# Port.net
KiCad netlist of a schematic drawn in Altium Designer
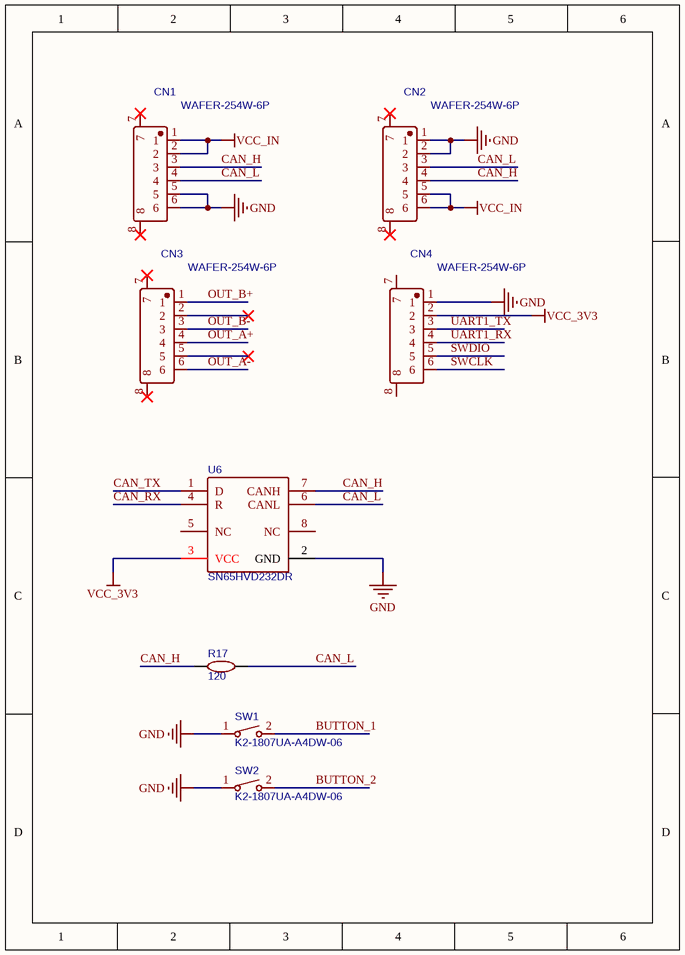
[diagram p0: Port.SchDoc]

(export (version "E")
  (design (tool "Eeschema 10.0.6"))
  (components
    (comp (ref "CN1")
      (value "WAFER-254W-6P")
      (footprint "CONN-SMD_WAFER-254W-6P")
      (fields (field (name "BOM_SUPPLIER PART") "C2856747") (field (name "CONTRIBUTOR") "LCSC"))
      (libsource (lib "6P 2.54mm") (part "WAFER-254W-6P"))
    )
    (comp (ref "CN2")
      (value "WAFER-254W-6P")
      (footprint "CONN-SMD_WAFER-254W-6P")
      (fields (field (name "BOM_SUPPLIER PART") "C2856747") (field (name "CONTRIBUTOR") "LCSC"))
      (libsource (lib "6P 2.54mm") (part "WAFER-254W-6P"))
    )
    (comp (ref "CN3")
      (value "WAFER-254W-6P")
      (footprint "CONN-SMD_WAFER-254W-6P")
      (fields (field (name "BOM_SUPPLIER PART") "C2856747") (field (name "CONTRIBUTOR") "LCSC"))
      (libsource (lib "6P 2.54mm") (part "WAFER-254W-6P"))
    )
    (comp (ref "CN4")
      (value "WAFER-254W-6P")
      (footprint "CONN-SMD_WAFER-254W-6P")
      (fields (field (name "BOM_SUPPLIER PART") "C2856747") (field (name "CONTRIBUTOR") "LCSC"))
      (libsource (lib "6P 2.54mm") (part "WAFER-254W-6P"))
    )
    (comp (ref "R17")
      (value "120")
      (footprint "R0603")
      (fields
        (field (name "BOM_MANUFACTURER PART") "0603WAF1200T5E")
        (field (name "BOM_SUPPLIER PART") "C22787")
      )
      (libsource (lib "120R") (part "120"))
    )
    (comp (ref "SW1")
      (value "K2-1807UA-A4DW-06")
      (footprint "KEY-SMD_L4.0-W2.9-L")
      (fields (field (name "BOM_SUPPLIER PART") "C502307") (field (name "CONTRIBUTOR") "LCSC"))
      (libsource (lib "BUTTON") (part "K2-1807UA-A4DW-06"))
    )
    (comp (ref "SW2")
      (value "K2-1807UA-A4DW-06")
      (footprint "KEY-SMD_L4.0-W2.9-L")
      (fields (field (name "BOM_SUPPLIER PART") "C502307") (field (name "CONTRIBUTOR") "LCSC"))
      (libsource (lib "BUTTON") (part "K2-1807UA-A4DW-06"))
    )
    (comp (ref "U6")
      (value "SN65HVD232DR")
      (footprint "SOIC-8_L5.0-W4.0-P1.27-LS6.0-BL")
      (fields (field (name "BOM_SUPPLIER PART") "C30530"))
      (libsource (lib "SN65HVD232DR") (part "SN65HVD232DR"))
    )
  )
  (nets
    (net (code "1") (name "/BUTTON_1") (class "Default")
      (node (ref "SW1") (pin "2") (pinfunction "2_2") (pintype "passive"))
    )
    (net (code "2") (name "/BUTTON_2") (class "Default")
      (node (ref "SW2") (pin "2") (pinfunction "2_2") (pintype "passive"))
    )
    (net (code "3") (name "/CAN_H") (class "Default")
      (node (ref "CN1") (pin "3") (pinfunction "3_3") (pintype "passive"))
      (node (ref "CN2") (pin "4") (pinfunction "4_4") (pintype "passive"))
      (node (ref "R17") (pin "1") (pinfunction "1_1") (pintype "passive"))
      (node (ref "U6") (pin "7") (pinfunction "CANH_7") (pintype "passive"))
    )
    (net (code "4") (name "/CAN_L") (class "Default")
      (node (ref "CN1") (pin "4") (pinfunction "4_4") (pintype "passive"))
      (node (ref "CN2") (pin "3") (pinfunction "3_3") (pintype "passive"))
      (node (ref "R17") (pin "2") (pinfunction "2_2") (pintype "passive"))
      (node (ref "U6") (pin "6") (pinfunction "CANL_6") (pintype "passive"))
    )
    (net (code "5") (name "/CAN_RX") (class "Default")
      (node (ref "U6") (pin "4") (pinfunction "R_4") (pintype "passive"))
    )
    (net (code "6") (name "/CAN_TX") (class "Default")
      (node (ref "U6") (pin "1") (pinfunction "D_1") (pintype "passive"))
    )
    (net (code "7") (name "/OUT_A+") (class "Default")
      (node (ref "CN3") (pin "4") (pinfunction "4_4") (pintype "passive"))
    )
    (net (code "8") (name "/OUT_A-") (class "Default")
      (node (ref "CN3") (pin "6") (pinfunction "6_6") (pintype "passive"))
    )
    (net (code "9") (name "/OUT_B+") (class "Default")
      (node (ref "CN3") (pin "1") (pinfunction "1_1") (pintype "passive"))
    )
    (net (code "10") (name "/OUT_B-") (class "Default")
      (node (ref "CN3") (pin "3") (pinfunction "3_3") (pintype "passive"))
    )
    (net (code "11") (name "/SWCLK") (class "Default")
      (node (ref "CN4") (pin "6") (pinfunction "6_6") (pintype "passive"))
    )
    (net (code "12") (name "/SWDIO") (class "Default")
      (node (ref "CN4") (pin "5") (pinfunction "5_5") (pintype "passive"))
    )
    (net (code "13") (name "/UART1_RX") (class "Default")
      (node (ref "CN4") (pin "4") (pinfunction "4_4") (pintype "passive"))
    )
    (net (code "14") (name "/UART1_TX") (class "Default")
      (node (ref "CN4") (pin "3") (pinfunction "3_3") (pintype "passive"))
    )
    (net (code "15") (name "GND") (class "Default")
      (node (ref "CN1") (pin "5") (pinfunction "5_5") (pintype "passive"))
      (node (ref "CN1") (pin "6") (pinfunction "6_6") (pintype "passive"))
      (node (ref "CN2") (pin "1") (pinfunction "1_1") (pintype "passive"))
      (node (ref "CN2") (pin "2") (pinfunction "2_2") (pintype "passive"))
      (node (ref "CN4") (pin "1") (pinfunction "1_1") (pintype "passive"))
      (node (ref "SW1") (pin "1") (pinfunction "1_1") (pintype "passive"))
      (node (ref "SW2") (pin "1") (pinfunction "1_1") (pintype "passive"))
      (node (ref "U6") (pin "2") (pinfunction "GND_2") (pintype "passive"))
    )
    (net (code "16") (name "VCC_3V3") (class "Default")
      (node (ref "CN4") (pin "2") (pinfunction "2_2") (pintype "passive"))
      (node (ref "U6") (pin "3") (pinfunction "VCC_3") (pintype "passive"))
    )
    (net (code "17") (name "VCC_IN") (class "Default")
      (node (ref "CN1") (pin "1") (pinfunction "1_1") (pintype "passive"))
      (node (ref "CN1") (pin "2") (pinfunction "2_2") (pintype "passive"))
      (node (ref "CN2") (pin "5") (pinfunction "5_5") (pintype "passive"))
      (node (ref "CN2") (pin "6") (pinfunction "6_6") (pintype "passive"))
    )
    (net (code "18") (name "unconnected-(CN1-Pad7)") (class "Default")
      (node (ref "CN1") (pin "7") (pinfunction "7_7") (pintype "passive+no_connect"))
    )
    (net (code "19") (name "unconnected-(CN1-Pad8)") (class "Default")
      (node (ref "CN1") (pin "8") (pinfunction "8_8") (pintype "passive+no_connect"))
    )
    (net (code "20") (name "unconnected-(CN2-Pad7)") (class "Default")
      (node (ref "CN2") (pin "7") (pinfunction "7_7") (pintype "passive+no_connect"))
    )
    (net (code "21") (name "unconnected-(CN2-Pad8)") (class "Default")
      (node (ref "CN2") (pin "8") (pinfunction "8_8") (pintype "passive+no_connect"))
    )
    (net (code "22") (name "unconnected-(CN3-Pad2)") (class "Default")
      (node (ref "CN3") (pin "2") (pinfunction "2_2") (pintype "passive+no_connect"))
    )
    (net (code "23") (name "unconnected-(CN3-Pad5)") (class "Default")
      (node (ref "CN3") (pin "5") (pinfunction "5_5") (pintype "passive+no_connect"))
    )
    (net (code "24") (name "unconnected-(CN3-Pad7)") (class "Default")
      (node (ref "CN3") (pin "7") (pinfunction "7_7") (pintype "passive+no_connect"))
    )
    (net (code "25") (name "unconnected-(CN3-Pad8)") (class "Default")
      (node (ref "CN3") (pin "8") (pinfunction "8_8") (pintype "passive+no_connect"))
    )
    (net (code "26") (name "unconnected-(CN4-Pad7)") (class "Default")
      (node (ref "CN4") (pin "7") (pinfunction "7_7") (pintype "passive"))
    )
    (net (code "27") (name "unconnected-(CN4-Pad8)") (class "Default")
      (node (ref "CN4") (pin "8") (pinfunction "8_8") (pintype "passive"))
    )
    (net (code "28") (name "unconnected-(U6-NC-Pad5)") (class "Default")
      (node (ref "U6") (pin "5") (pinfunction "NC_5") (pintype "passive"))
    )
    (net (code "29") (name "unconnected-(U6-NC-Pad8)") (class "Default")
      (node (ref "U6") (pin "8") (pinfunction "NC_8") (pintype "passive"))
    )
  )
)
